# Joystick_Module_A.net
KiCad netlist of a schematic drawn in EAGLE
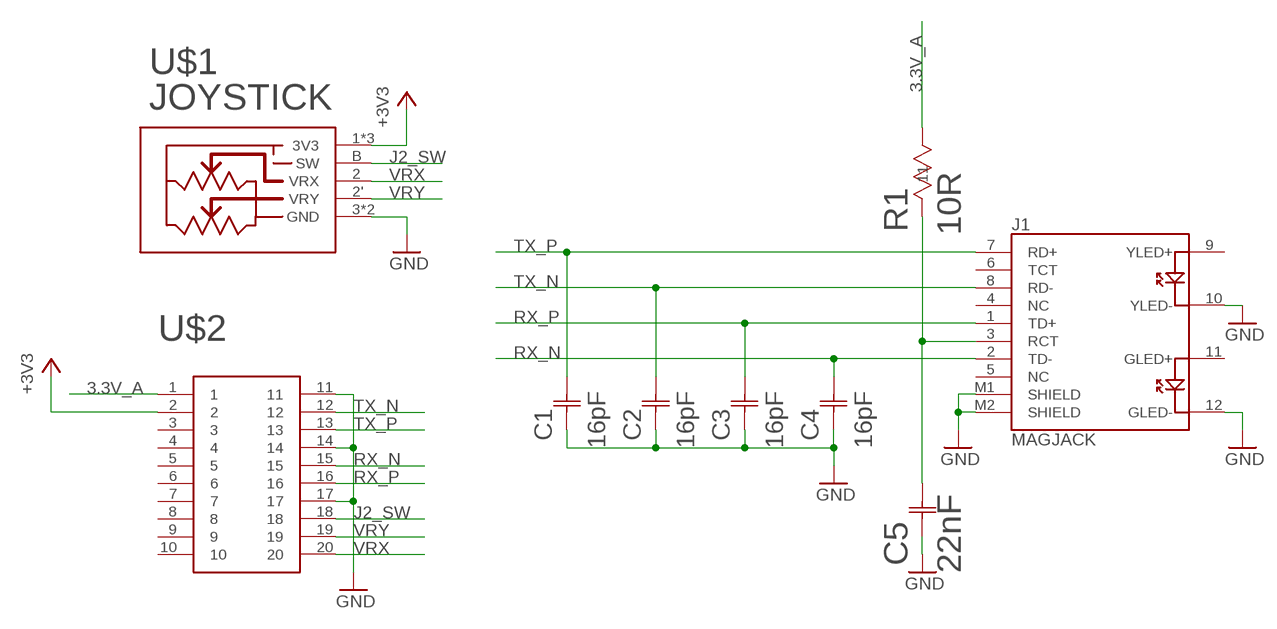
[diagram p0: schematic, sheet 1]

(export (version "E")
  (design (tool "Eeschema 10.0.6"))
  (components
    (comp (ref "C1")
      (value "16pF")
      (footprint "eagle-import:G-155-M")
      (fields (field (name "MANUFACTURER_PART_NUMBER") "GRM1555C1H160JA01D"))
      (libsource (lib "eagle-import") (part "GRM1555C1H160JA01DG-155-M"))
    )
    (comp (ref "C2")
      (value "16pF")
      (footprint "eagle-import:G-155-M")
      (fields (field (name "MANUFACTURER_PART_NUMBER") "GRM1555C1H160JA01D"))
      (libsource (lib "eagle-import") (part "GRM1555C1H160JA01DG-155-M"))
    )
    (comp (ref "C3")
      (value "16pF")
      (footprint "eagle-import:G-155-M")
      (fields (field (name "MANUFACTURER_PART_NUMBER") "GRM1555C1H160JA01D"))
      (libsource (lib "eagle-import") (part "GRM1555C1H160JA01DG-155-M"))
    )
    (comp (ref "C4")
      (value "16pF")
      (footprint "eagle-import:G-155-M")
      (fields (field (name "MANUFACTURER_PART_NUMBER") "GRM1555C1H160JA01D"))
      (libsource (lib "eagle-import") (part "GRM1555C1H160JA01DG-155-M"))
    )
    (comp (ref "C5")
      (value "22nF")
      (footprint "eagle-import:G-155-M")
      (fields (field (name "MANUFACTURER_PART_NUMBER") "GRM155R71H223KA12D"))
      (libsource (lib "eagle-import") (part "GRM155R71H223KA12DG-155-M"))
    )
    (comp (ref "J1")
      (value "MAGJACK")
      (footprint "eagle-import:MAGJACK")
      (libsource (lib "eagle-import") (part "MAGJACK"))
    )
    (comp (ref "R1")
      (value "10R")
      (footprint "eagle-import:STA_RNCP0805-M")
      (fields
        (field (name "MANUFACTURER_PART_NUMBER") "RNCP0805FTD10R0")
        (field (name "COPYRIGHT") "Copyright C 2015 Accelerated Designs. All rights reserved")
      )
      (libsource (lib "eagle-import") (part "RNCP0805FTD10R0STA_RNCP0805-M"))
    )
    (comp (ref "U$1")
      (value "JOYSTICK\"")
      (footprint "eagle-import:JOYSTICK")
      (libsource (lib "eagle-import") (part "JOYSTICK{dblquote}"))
    )
    (comp (ref "U$2")
      (value "EDGE_CONNECTOR_20POS_CONTACTS")
      (footprint "eagle-import:EDGE_CONNECTOR_20POS_CONTACTS")
      (libsource (lib "eagle-import") (part "EDGE_CONNECTOR_20POS_CONTACTS"))
    )
  )
  (nets
    (net (code "1") (name "+3V3") (class "Default")
      (node (ref "U$1") (pin "1") (pinfunction "3V3_1") (pintype "power_in"))
      (node (ref "U$1") (pin "1'") (pinfunction "3V3_1'") (pintype "power_in"))
      (node (ref "U$1") (pin "A") (pinfunction "3V3_A") (pintype "power_in"))
      (node (ref "U$2") (pin "2") (pinfunction "2_2") (pintype "bidirectional"))
    )
    (net (code "2") (name "/3.3V_A") (class "Default")
      (node (ref "R1") (pin "2") (pinfunction "22_2") (pintype "passive"))
      (node (ref "U$2") (pin "1") (pinfunction "1_1") (pintype "bidirectional"))
    )
    (net (code "3") (name "/J2_SW") (class "Default")
      (node (ref "U$1") (pin "B") (pinfunction "SW_B") (pintype "bidirectional"))
      (node (ref "U$2") (pin "18") (pinfunction "18_18") (pintype "bidirectional"))
    )
    (net (code "4") (name "/RX_N") (class "Default")
      (node (ref "C4") (pin "2") (pinfunction "22_2") (pintype "passive"))
      (node (ref "J1") (pin "2") (pinfunction "TD-_2") (pintype "bidirectional"))
      (node (ref "U$2") (pin "15") (pinfunction "15_15") (pintype "bidirectional"))
    )
    (net (code "5") (name "/RX_P") (class "Default")
      (node (ref "C3") (pin "2") (pinfunction "22_2") (pintype "passive"))
      (node (ref "J1") (pin "1") (pinfunction "TD+_1") (pintype "bidirectional"))
      (node (ref "U$2") (pin "16") (pinfunction "16_16") (pintype "bidirectional"))
    )
    (net (code "6") (name "/TX_N") (class "Default")
      (node (ref "C2") (pin "2") (pinfunction "22_2") (pintype "passive"))
      (node (ref "J1") (pin "8") (pinfunction "RD-_8") (pintype "bidirectional"))
      (node (ref "U$2") (pin "12") (pinfunction "12_12") (pintype "bidirectional"))
    )
    (net (code "7") (name "/TX_P") (class "Default")
      (node (ref "C1") (pin "2") (pinfunction "22_2") (pintype "passive"))
      (node (ref "J1") (pin "7") (pinfunction "RD+_7") (pintype "bidirectional"))
      (node (ref "U$2") (pin "13") (pinfunction "13_13") (pintype "bidirectional"))
    )
    (net (code "8") (name "/VRX") (class "Default")
      (node (ref "U$1") (pin "2") (pinfunction "VRX_2") (pintype "bidirectional"))
      (node (ref "U$2") (pin "20") (pinfunction "20_20") (pintype "bidirectional"))
    )
    (net (code "9") (name "/VRY") (class "Default")
      (node (ref "U$1") (pin "2'") (pinfunction "VRY_2'") (pintype "bidirectional"))
      (node (ref "U$2") (pin "19") (pinfunction "19_19") (pintype "bidirectional"))
    )
    (net (code "10") (name "GND") (class "Default")
      (node (ref "C1") (pin "1") (pinfunction "11_1") (pintype "passive"))
      (node (ref "C2") (pin "1") (pinfunction "11_1") (pintype "passive"))
      (node (ref "C3") (pin "1") (pinfunction "11_1") (pintype "passive"))
      (node (ref "C4") (pin "1") (pinfunction "11_1") (pintype "passive"))
      (node (ref "C5") (pin "1") (pinfunction "11_1") (pintype "passive"))
      (node (ref "J1") (pin "10") (pinfunction "YLED-_10") (pintype "bidirectional"))
      (node (ref "J1") (pin "12") (pinfunction "GLED-_12") (pintype "bidirectional"))
      (node (ref "J1") (pin "M1") (pinfunction "SHIELD_M1") (pintype "bidirectional"))
      (node (ref "J1") (pin "M2") (pinfunction "SHIELD_M2") (pintype "bidirectional"))
      (node (ref "U$1") (pin "3") (pinfunction "GND_3") (pintype "power_in"))
      (node (ref "U$1") (pin "3'") (pinfunction "GND_3'") (pintype "power_in"))
      (node (ref "U$2") (pin "11") (pinfunction "11_11") (pintype "bidirectional"))
      (node (ref "U$2") (pin "14") (pinfunction "14_14") (pintype "bidirectional"))
      (node (ref "U$2") (pin "17") (pinfunction "17_17") (pintype "bidirectional"))
    )
    (net (code "11") (name "Net-(C5-22)") (class "Default")
      (node (ref "C5") (pin "2") (pinfunction "22_2") (pintype "passive"))
      (node (ref "J1") (pin "3") (pinfunction "RCT_3") (pintype "bidirectional"))
      (node (ref "R1") (pin "1") (pinfunction "11_1") (pintype "passive"))
    )
    (net (code "12") (name "unconnected-(J1-GLED+-Pad11)") (class "Default")
      (node (ref "J1") (pin "11") (pinfunction "GLED+_11") (pintype "bidirectional"))
    )
    (net (code "13") (name "unconnected-(J1-NC-Pad4)") (class "Default")
      (node (ref "J1") (pin "4") (pinfunction "NC_4") (pintype "bidirectional"))
    )
    (net (code "14") (name "unconnected-(J1-NC-Pad5)") (class "Default")
      (node (ref "J1") (pin "5") (pinfunction "NC_5") (pintype "bidirectional"))
    )
    (net (code "15") (name "unconnected-(J1-TCT-Pad6)") (class "Default")
      (node (ref "J1") (pin "6") (pinfunction "TCT_6") (pintype "bidirectional"))
    )
    (net (code "16") (name "unconnected-(J1-YLED+-Pad9)") (class "Default")
      (node (ref "J1") (pin "9") (pinfunction "YLED+_9") (pintype "bidirectional"))
    )
    (net (code "17") (name "unconnected-(U$2-Pad3)") (class "Default")
      (node (ref "U$2") (pin "3") (pinfunction "3_3") (pintype "bidirectional"))
    )
    (net (code "18") (name "unconnected-(U$2-Pad4)") (class "Default")
      (node (ref "U$2") (pin "4") (pinfunction "4_4") (pintype "bidirectional"))
    )
    (net (code "19") (name "unconnected-(U$2-Pad5)") (class "Default")
      (node (ref "U$2") (pin "5") (pinfunction "5_5") (pintype "bidirectional"))
    )
    (net (code "20") (name "unconnected-(U$2-Pad6)") (class "Default")
      (node (ref "U$2") (pin "6") (pinfunction "6_6") (pintype "bidirectional"))
    )
    (net (code "21") (name "unconnected-(U$2-Pad7)") (class "Default")
      (node (ref "U$2") (pin "7") (pinfunction "7_7") (pintype "bidirectional"))
    )
    (net (code "22") (name "unconnected-(U$2-Pad8)") (class "Default")
      (node (ref "U$2") (pin "8") (pinfunction "8_8") (pintype "bidirectional"))
    )
    (net (code "23") (name "unconnected-(U$2-Pad9)") (class "Default")
      (node (ref "U$2") (pin "9") (pinfunction "9_9") (pintype "bidirectional"))
    )
    (net (code "24") (name "unconnected-(U$2-Pad10)") (class "Default")
      (node (ref "U$2") (pin "10") (pinfunction "10_10") (pintype "bidirectional"))
    )
  )
)
